# CONNECTOR.net
KiCad netlist of a schematic drawn in Altium Designer
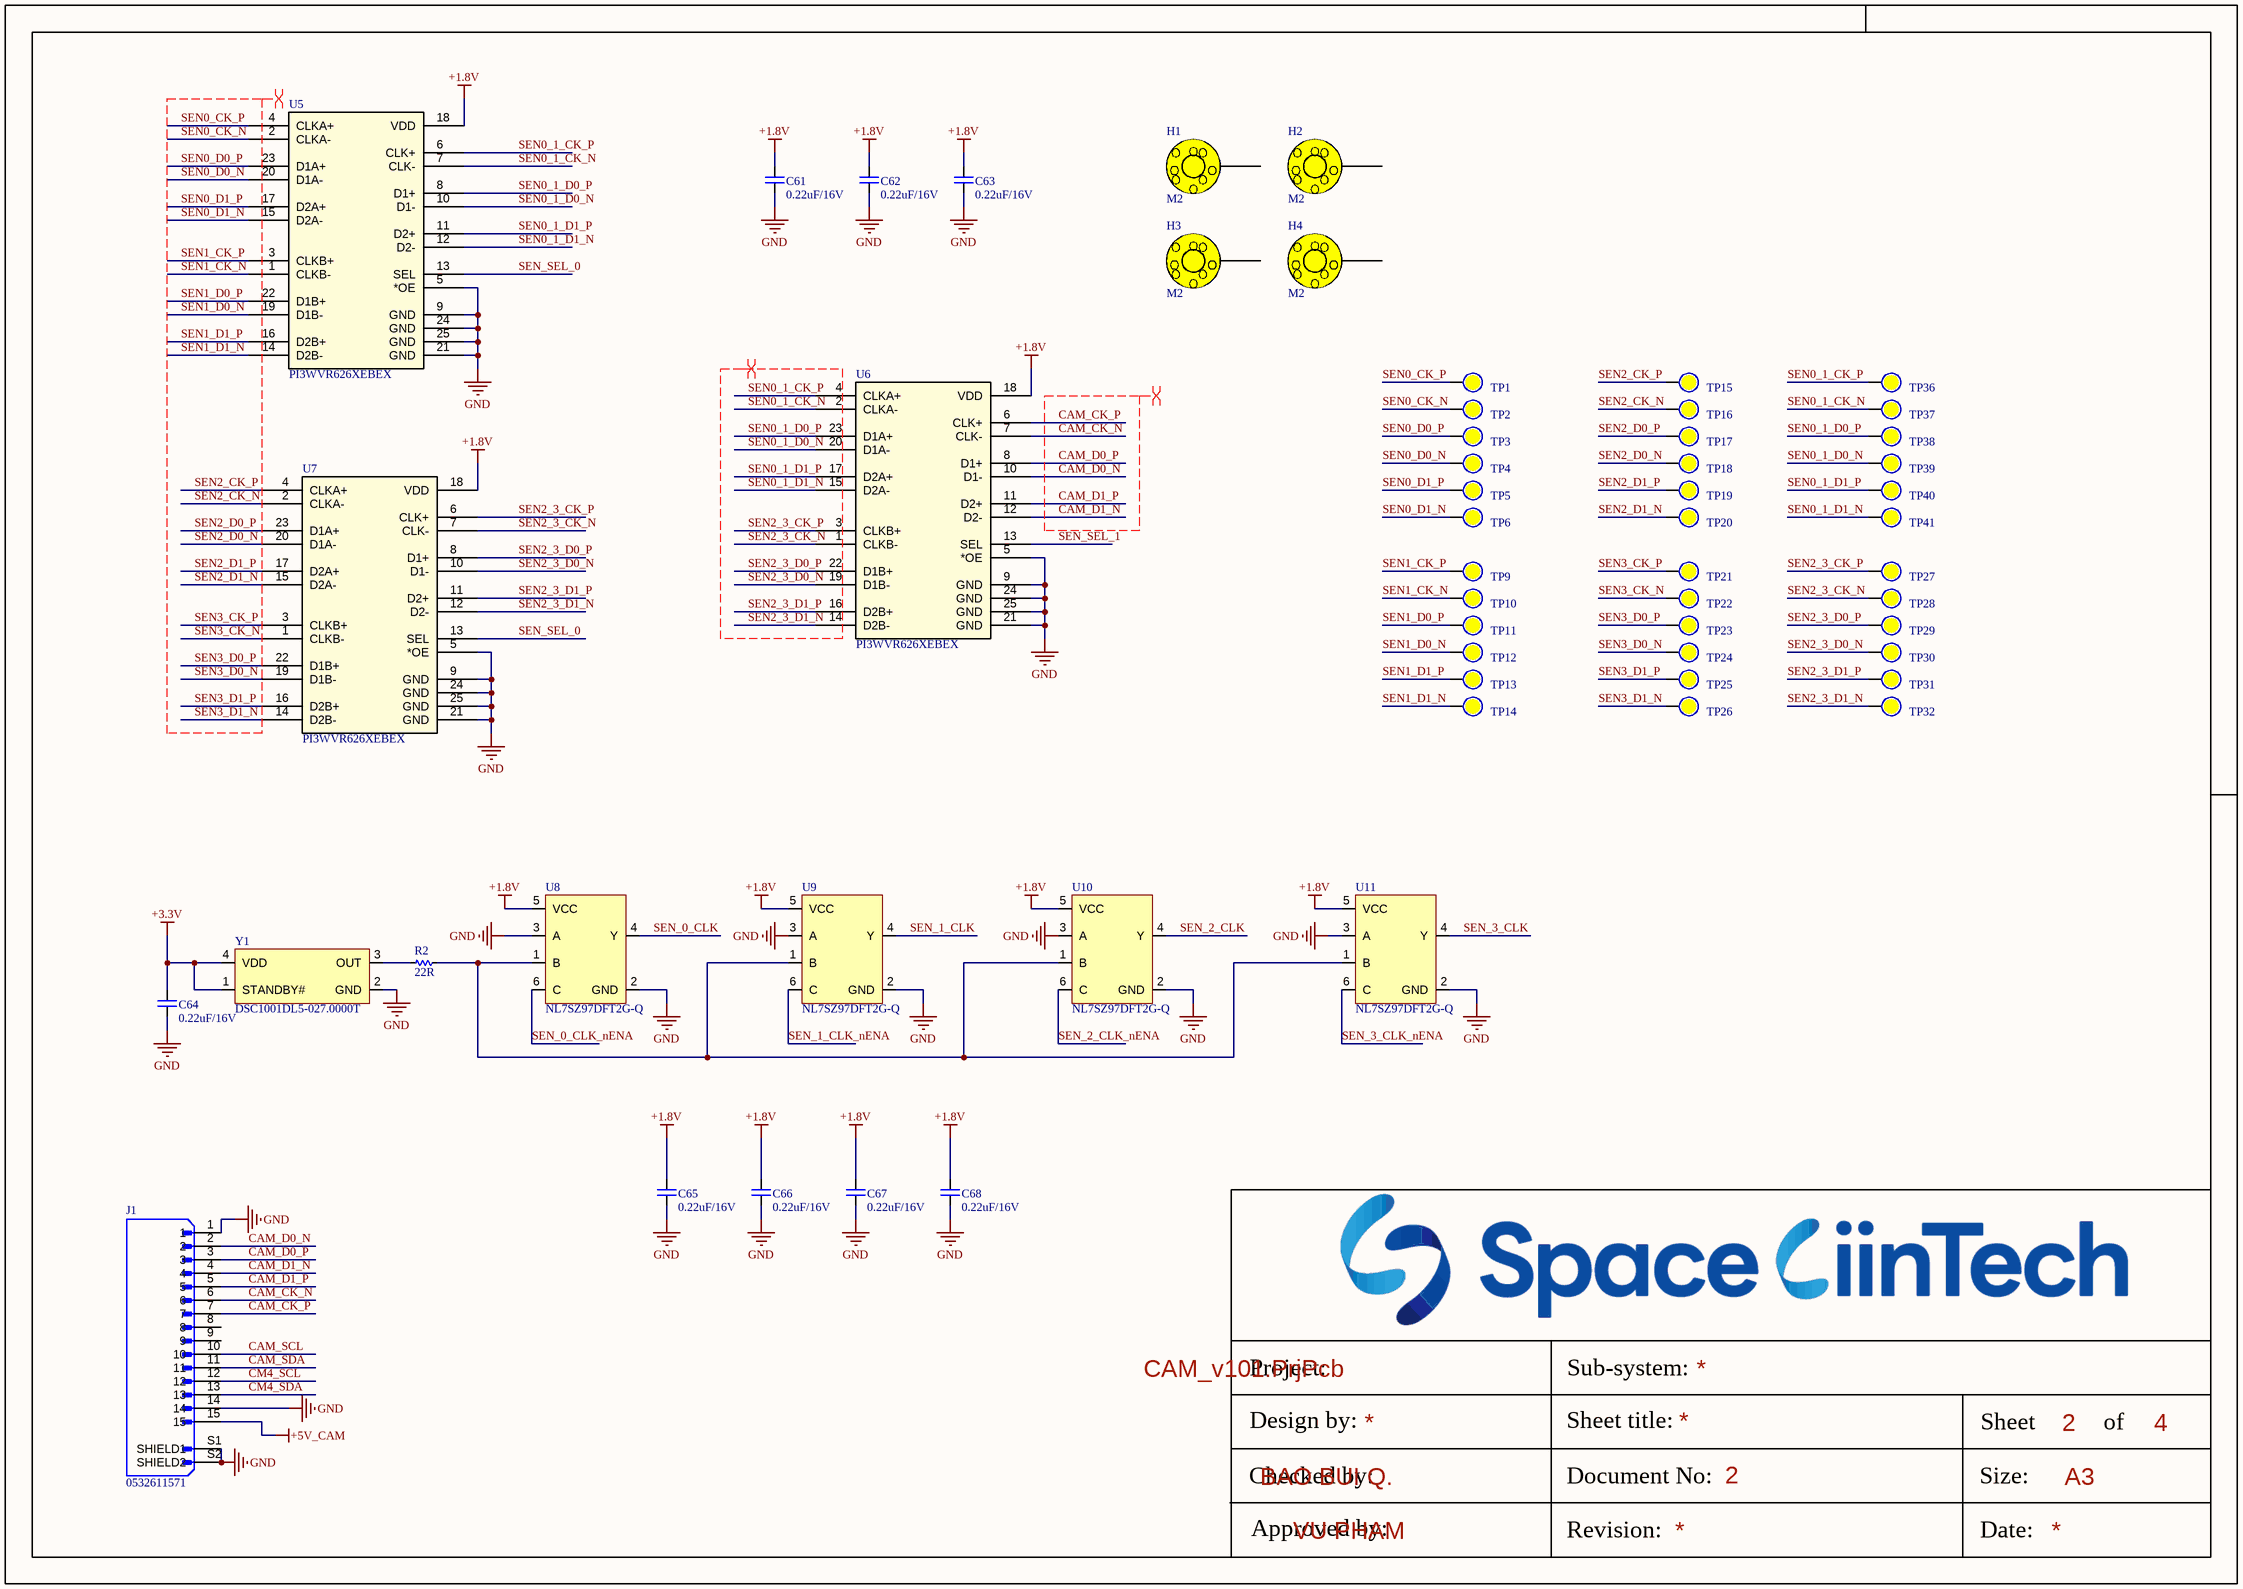
[diagram p0: CONNECTOR.SchDoc]

(export (version "E")
  (design (tool "Eeschema 10.0.6"))
  (components
    (comp (ref "C61")
      (value "0.22uF/16V")
      (footprint "CAP_C_1005X60")
      (description "CAP_Chip")
      (libsource (lib "LABLIB") (part "CAP_SMD"))
    )
    (comp (ref "C62")
      (value "0.22uF/16V")
      (footprint "CAP_C_1005X60")
      (description "CAP_Chip")
      (libsource (lib "LABLIB") (part "CAP_SMD"))
    )
    (comp (ref "C63")
      (value "0.22uF/16V")
      (footprint "CAP_C_1005X60")
      (description "CAP_Chip")
      (libsource (lib "LABLIB") (part "CAP_SMD"))
    )
    (comp (ref "C64")
      (value "0.22uF/16V")
      (footprint "CAP_C_1005X60")
      (description "CAP_Chip")
      (libsource (lib "LABLIB") (part "CAP_SMD"))
    )
    (comp (ref "C65")
      (value "0.22uF/16V")
      (footprint "CAP_C_1005X60")
      (description "CAP_Chip")
      (libsource (lib "LABLIB") (part "CAP_SMD"))
    )
    (comp (ref "C66")
      (value "0.22uF/16V")
      (footprint "CAP_C_1005X60")
      (description "CAP_Chip")
      (libsource (lib "LABLIB") (part "CAP_SMD"))
    )
    (comp (ref "C67")
      (value "0.22uF/16V")
      (footprint "CAP_C_1005X60")
      (description "CAP_Chip")
      (libsource (lib "LABLIB") (part "CAP_SMD"))
    )
    (comp (ref "C68")
      (value "0.22uF/16V")
      (footprint "CAP_C_1005X60")
      (description "CAP_Chip")
      (libsource (lib "LABLIB") (part "CAP_SMD"))
    )
    (comp (ref "H1") (value "M2") (footprint "HEX-2.2mm") (libsource (lib "hex_M3") (part "HEX-M3")))
    (comp (ref "H2") (value "M2") (footprint "HEX-2.2mm") (libsource (lib "hex_M3") (part "HEX-M3")))
    (comp (ref "H3") (value "M2") (footprint "HEX-2.2mm") (libsource (lib "hex_M3") (part "HEX-M3")))
    (comp (ref "H4") (value "M2") (footprint "HEX-2.2mm") (libsource (lib "hex_M3") (part "HEX-M3")))
    (comp (ref "J1")
      (value "0532611571")
      (footprint "0532611571")
      (description "Conn Shrouded Header (4 Sides) HDR 15 POS 1.25mm Solder RA Side Entry SMD PicoBladeâ„¢ T/R")
      (fields (field (name "MP") "532611571") (field (name "MF") "Molex"))
      (libsource (lib "EXP_HW_V2") (part "CONN_SMD_15"))
    )
    (comp (ref "R2")
      (value "22R")
      (footprint "RES_C_1005X40")
      (description "RES-Chip")
      (fields
        (field (name "MANUFACTURER") "Generic Components")
        (field (name "PUBLISHER") "Altium Hobart Technology Centre")
      )
      (libsource (lib "LABLIB") (part "RES-SMD"))
    )
    (comp (ref "TP1")
      (value "~")
      (footprint "Testpoint_60")
      (description "Test Point")
      (libsource (lib "LABLIB") (part "Test Point"))
    )
    (comp (ref "TP2")
      (value "~")
      (footprint "Testpoint_60")
      (description "Test Point")
      (libsource (lib "LABLIB") (part "Test Point"))
    )
    (comp (ref "TP3")
      (value "~")
      (footprint "Testpoint_60")
      (description "Test Point")
      (libsource (lib "LABLIB") (part "Test Point"))
    )
    (comp (ref "TP4")
      (value "~")
      (footprint "Testpoint_60")
      (description "Test Point")
      (libsource (lib "LABLIB") (part "Test Point"))
    )
    (comp (ref "TP5")
      (value "~")
      (footprint "Testpoint_60")
      (description "Test Point")
      (libsource (lib "LABLIB") (part "Test Point"))
    )
    (comp (ref "TP6")
      (value "~")
      (footprint "Testpoint_60")
      (description "Test Point")
      (libsource (lib "LABLIB") (part "Test Point"))
    )
    (comp (ref "TP9")
      (value "~")
      (footprint "Testpoint_60")
      (description "Test Point")
      (libsource (lib "LABLIB") (part "Test Point"))
    )
    (comp (ref "TP10")
      (value "~")
      (footprint "Testpoint_60")
      (description "Test Point")
      (libsource (lib "LABLIB") (part "Test Point"))
    )
    (comp (ref "TP11")
      (value "~")
      (footprint "Testpoint_60")
      (description "Test Point")
      (libsource (lib "LABLIB") (part "Test Point"))
    )
    (comp (ref "TP12")
      (value "~")
      (footprint "Testpoint_60")
      (description "Test Point")
      (libsource (lib "LABLIB") (part "Test Point"))
    )
    (comp (ref "TP13")
      (value "~")
      (footprint "Testpoint_60")
      (description "Test Point")
      (libsource (lib "LABLIB") (part "Test Point"))
    )
    (comp (ref "TP14")
      (value "~")
      (footprint "Testpoint_60")
      (description "Test Point")
      (libsource (lib "LABLIB") (part "Test Point"))
    )
    (comp (ref "TP15")
      (value "~")
      (footprint "Testpoint_60")
      (description "Test Point")
      (libsource (lib "LABLIB") (part "Test Point"))
    )
    (comp (ref "TP16")
      (value "~")
      (footprint "Testpoint_60")
      (description "Test Point")
      (libsource (lib "LABLIB") (part "Test Point"))
    )
    (comp (ref "TP17")
      (value "~")
      (footprint "Testpoint_60")
      (description "Test Point")
      (libsource (lib "LABLIB") (part "Test Point"))
    )
    (comp (ref "TP18")
      (value "~")
      (footprint "Testpoint_60")
      (description "Test Point")
      (libsource (lib "LABLIB") (part "Test Point"))
    )
    (comp (ref "TP19")
      (value "~")
      (footprint "Testpoint_60")
      (description "Test Point")
      (libsource (lib "LABLIB") (part "Test Point"))
    )
    (comp (ref "TP20")
      (value "~")
      (footprint "Testpoint_60")
      (description "Test Point")
      (libsource (lib "LABLIB") (part "Test Point"))
    )
    (comp (ref "TP21")
      (value "~")
      (footprint "Testpoint_60")
      (description "Test Point")
      (libsource (lib "LABLIB") (part "Test Point"))
    )
    (comp (ref "TP22")
      (value "~")
      (footprint "Testpoint_60")
      (description "Test Point")
      (libsource (lib "LABLIB") (part "Test Point"))
    )
    (comp (ref "TP23")
      (value "~")
      (footprint "Testpoint_60")
      (description "Test Point")
      (libsource (lib "LABLIB") (part "Test Point"))
    )
    (comp (ref "TP24")
      (value "~")
      (footprint "Testpoint_60")
      (description "Test Point")
      (libsource (lib "LABLIB") (part "Test Point"))
    )
    (comp (ref "TP25")
      (value "~")
      (footprint "Testpoint_60")
      (description "Test Point")
      (libsource (lib "LABLIB") (part "Test Point"))
    )
    (comp (ref "TP26")
      (value "~")
      (footprint "Testpoint_60")
      (description "Test Point")
      (libsource (lib "LABLIB") (part "Test Point"))
    )
    (comp (ref "TP27")
      (value "~")
      (footprint "Testpoint_50")
      (description "Test Point")
      (libsource (lib "LABLIB") (part "Test Point"))
    )
    (comp (ref "TP28")
      (value "~")
      (footprint "Testpoint_50")
      (description "Test Point")
      (libsource (lib "LABLIB") (part "Test Point"))
    )
    (comp (ref "TP29")
      (value "~")
      (footprint "Testpoint_50")
      (description "Test Point")
      (libsource (lib "LABLIB") (part "Test Point"))
    )
    (comp (ref "TP30")
      (value "~")
      (footprint "Testpoint_50")
      (description "Test Point")
      (libsource (lib "LABLIB") (part "Test Point"))
    )
    (comp (ref "TP31")
      (value "~")
      (footprint "Testpoint_50")
      (description "Test Point")
      (libsource (lib "LABLIB") (part "Test Point"))
    )
    (comp (ref "TP32")
      (value "~")
      (footprint "Testpoint_50")
      (description "Test Point")
      (libsource (lib "LABLIB") (part "Test Point"))
    )
    (comp (ref "TP36")
      (value "~")
      (footprint "Testpoint_50")
      (description "Test Point")
      (libsource (lib "LABLIB") (part "Test Point"))
    )
    (comp (ref "TP37")
      (value "~")
      (footprint "Testpoint_50")
      (description "Test Point")
      (libsource (lib "LABLIB") (part "Test Point"))
    )
    (comp (ref "TP38")
      (value "~")
      (footprint "Testpoint_50")
      (description "Test Point")
      (libsource (lib "LABLIB") (part "Test Point"))
    )
    (comp (ref "TP39")
      (value "~")
      (footprint "Testpoint_50")
      (description "Test Point")
      (libsource (lib "LABLIB") (part "Test Point"))
    )
    (comp (ref "TP40")
      (value "~")
      (footprint "Testpoint_50")
      (description "Test Point")
      (libsource (lib "LABLIB") (part "Test Point"))
    )
    (comp (ref "TP41")
      (value "~")
      (footprint "Testpoint_50")
      (description "Test Point")
      (libsource (lib "LABLIB") (part "Test Point"))
    )
    (comp (ref "U5")
      (value "PI3WVR626XEBEX")
      (footprint "PI3WVR626XEBEX_DIO_2")
      (libsource (lib "CAMERA_SchLib") (part "PI3WVR626XEBEX"))
    )
    (comp (ref "U6")
      (value "PI3WVR626XEBEX")
      (footprint "PI3WVR626XEBEX_DIO_2")
      (libsource (lib "CAMERA_SchLib") (part "PI3WVR626XEBEX"))
    )
    (comp (ref "U7")
      (value "PI3WVR626XEBEX")
      (footprint "PI3WVR626XEBEX_DIO_2")
      (libsource (lib "CAMERA_SchLib") (part "PI3WVR626XEBEX"))
    )
    (comp (ref "U8")
      (value "NL7SZ97DFT2G-Q")
      (footprint "SC-88")
      (libsource (lib "CAMERA_SchLib") (part "IC_FLEXLOGIC_NL7SZ97DFT2G-Q"))
    )
    (comp (ref "U9")
      (value "NL7SZ97DFT2G-Q")
      (footprint "SC-88")
      (libsource (lib "CAMERA_SchLib") (part "IC_FLEXLOGIC_NL7SZ97DFT2G-Q"))
    )
    (comp (ref "U10")
      (value "NL7SZ97DFT2G-Q")
      (footprint "SC-88")
      (libsource (lib "CAMERA_SchLib") (part "IC_FLEXLOGIC_NL7SZ97DFT2G-Q"))
    )
    (comp (ref "U11")
      (value "NL7SZ97DFT2G-Q")
      (footprint "SC-88")
      (libsource (lib "CAMERA_SchLib") (part "IC_FLEXLOGIC_NL7SZ97DFT2G-Q"))
    )
    (comp (ref "Y1")
      (value "DSC1001DL5-027.0000T")
      (footprint "OSCDFN250X200X89-4N")
      (libsource (lib "CAMERA_SchLib") (part "Y_OSC27MHz_DSC1001DL5-027.0000T"))
    )
  )
  (nets
    (net (code "1") (name "+1.8V") (class "Default")
      (node (ref "C61") (pin "2") (pinfunction "2_2") (pintype "passive"))
      (node (ref "C62") (pin "2") (pinfunction "2_2") (pintype "passive"))
      (node (ref "C63") (pin "2") (pinfunction "2_2") (pintype "passive"))
      (node (ref "C65") (pin "2") (pinfunction "2_2") (pintype "passive"))
      (node (ref "C66") (pin "2") (pinfunction "2_2") (pintype "passive"))
      (node (ref "C67") (pin "2") (pinfunction "2_2") (pintype "passive"))
      (node (ref "C68") (pin "2") (pinfunction "2_2") (pintype "passive"))
      (node (ref "U10") (pin "5") (pinfunction "VCC_5") (pintype "passive"))
      (node (ref "U11") (pin "5") (pinfunction "VCC_5") (pintype "passive"))
      (node (ref "U5") (pin "18") (pinfunction "VDD_18") (pintype "passive"))
      (node (ref "U6") (pin "18") (pinfunction "VDD_18") (pintype "passive"))
      (node (ref "U7") (pin "18") (pinfunction "VDD_18") (pintype "passive"))
      (node (ref "U8") (pin "5") (pinfunction "VCC_5") (pintype "passive"))
      (node (ref "U9") (pin "5") (pinfunction "VCC_5") (pintype "passive"))
    )
    (net (code "2") (name "+3.3V") (class "Default")
      (node (ref "C64") (pin "2") (pinfunction "2_2") (pintype "passive"))
      (node (ref "Y1") (pin "1") (pinfunction "STANDBY#_1") (pintype "passive"))
      (node (ref "Y1") (pin "4") (pinfunction "VDD_4") (pintype "passive"))
    )
    (net (code "3") (name "+5V_CAM") (class "Default")
      (node (ref "J1") (pin "15") (pinfunction "15_15") (pintype "passive"))
    )
    (net (code "4") (name "/CAM_CK_N") (class "Default")
      (node (ref "J1") (pin "6") (pinfunction "6_6") (pintype "passive"))
      (node (ref "U6") (pin "7") (pinfunction "CLK-_7") (pintype "passive"))
    )
    (net (code "5") (name "/CAM_CK_P") (class "Default")
      (node (ref "J1") (pin "7") (pinfunction "7_7") (pintype "passive"))
      (node (ref "U6") (pin "6") (pinfunction "CLK+_6") (pintype "passive"))
    )
    (net (code "6") (name "/CAM_D0_N") (class "Default")
      (node (ref "J1") (pin "2") (pinfunction "2_2") (pintype "passive"))
      (node (ref "U6") (pin "10") (pinfunction "D1-_10") (pintype "passive"))
    )
    (net (code "7") (name "/CAM_D0_P") (class "Default")
      (node (ref "J1") (pin "3") (pinfunction "3_3") (pintype "passive"))
      (node (ref "U6") (pin "8") (pinfunction "D1+_8") (pintype "passive"))
    )
    (net (code "8") (name "/CAM_D1_N") (class "Default")
      (node (ref "J1") (pin "4") (pinfunction "4_4") (pintype "passive"))
      (node (ref "U6") (pin "12") (pinfunction "D2-_12") (pintype "passive"))
    )
    (net (code "9") (name "/CAM_D1_P") (class "Default")
      (node (ref "J1") (pin "5") (pinfunction "5_5") (pintype "passive"))
      (node (ref "U6") (pin "11") (pinfunction "D2+_11") (pintype "passive"))
    )
    (net (code "10") (name "/CAM_SCL") (class "Default")
      (node (ref "J1") (pin "10") (pinfunction "10_10") (pintype "passive"))
    )
    (net (code "11") (name "/CAM_SDA") (class "Default")
      (node (ref "J1") (pin "11") (pinfunction "11_11") (pintype "passive"))
    )
    (net (code "12") (name "/CM4_SCL") (class "Default")
      (node (ref "J1") (pin "12") (pinfunction "12_12") (pintype "passive"))
    )
    (net (code "13") (name "/CM4_SDA") (class "Default")
      (node (ref "J1") (pin "13") (pinfunction "13_13") (pintype "passive"))
    )
    (net (code "14") (name "/SEN0_1_CK_N") (class "Default")
      (node (ref "TP37") (pin "0") (pinfunction "0_0") (pintype "passive"))
      (node (ref "U5") (pin "7") (pinfunction "CLK-_7") (pintype "passive"))
      (node (ref "U6") (pin "2") (pinfunction "CLKA-_2") (pintype "passive"))
    )
    (net (code "15") (name "/SEN0_1_CK_P") (class "Default")
      (node (ref "TP36") (pin "0") (pinfunction "0_0") (pintype "passive"))
      (node (ref "U5") (pin "6") (pinfunction "CLK+_6") (pintype "passive"))
      (node (ref "U6") (pin "4") (pinfunction "CLKA+_4") (pintype "passive"))
    )
    (net (code "16") (name "/SEN0_1_D0_N") (class "Default")
      (node (ref "TP39") (pin "0") (pinfunction "0_0") (pintype "passive"))
      (node (ref "U5") (pin "10") (pinfunction "D1-_10") (pintype "passive"))
      (node (ref "U6") (pin "20") (pinfunction "D1A-_20") (pintype "passive"))
    )
    (net (code "17") (name "/SEN0_1_D0_P") (class "Default")
      (node (ref "TP38") (pin "0") (pinfunction "0_0") (pintype "passive"))
      (node (ref "U5") (pin "8") (pinfunction "D1+_8") (pintype "passive"))
      (node (ref "U6") (pin "23") (pinfunction "D1A+_23") (pintype "passive"))
    )
    (net (code "18") (name "/SEN0_1_D1_N") (class "Default")
      (node (ref "TP41") (pin "0") (pinfunction "0_0") (pintype "passive"))
      (node (ref "U5") (pin "12") (pinfunction "D2-_12") (pintype "passive"))
      (node (ref "U6") (pin "15") (pinfunction "D2A-_15") (pintype "passive"))
    )
    (net (code "19") (name "/SEN0_1_D1_P") (class "Default")
      (node (ref "TP40") (pin "0") (pinfunction "0_0") (pintype "passive"))
      (node (ref "U5") (pin "11") (pinfunction "D2+_11") (pintype "passive"))
      (node (ref "U6") (pin "17") (pinfunction "D2A+_17") (pintype "passive"))
    )
    (net (code "20") (name "/SEN0_CK_N") (class "Default")
      (node (ref "TP2") (pin "0") (pinfunction "0_0") (pintype "passive"))
      (node (ref "U5") (pin "2") (pinfunction "CLKA-_2") (pintype "passive"))
    )
    (net (code "21") (name "/SEN0_CK_P") (class "Default")
      (node (ref "TP1") (pin "0") (pinfunction "0_0") (pintype "passive"))
      (node (ref "U5") (pin "4") (pinfunction "CLKA+_4") (pintype "passive"))
    )
    (net (code "22") (name "/SEN0_D0_N") (class "Default")
      (node (ref "TP4") (pin "0") (pinfunction "0_0") (pintype "passive"))
      (node (ref "U5") (pin "20") (pinfunction "D1A-_20") (pintype "passive"))
    )
    (net (code "23") (name "/SEN0_D0_P") (class "Default")
      (node (ref "TP3") (pin "0") (pinfunction "0_0") (pintype "passive"))
      (node (ref "U5") (pin "23") (pinfunction "D1A+_23") (pintype "passive"))
    )
    (net (code "24") (name "/SEN0_D1_N") (class "Default")
      (node (ref "TP6") (pin "0") (pinfunction "0_0") (pintype "passive"))
      (node (ref "U5") (pin "15") (pinfunction "D2A-_15") (pintype "passive"))
    )
    (net (code "25") (name "/SEN0_D1_P") (class "Default")
      (node (ref "TP5") (pin "0") (pinfunction "0_0") (pintype "passive"))
      (node (ref "U5") (pin "17") (pinfunction "D2A+_17") (pintype "passive"))
    )
    (net (code "26") (name "/SEN1_CK_N") (class "Default")
      (node (ref "TP10") (pin "0") (pinfunction "0_0") (pintype "passive"))
      (node (ref "U5") (pin "1") (pinfunction "CLKB-_1") (pintype "passive"))
    )
    (net (code "27") (name "/SEN1_CK_P") (class "Default")
      (node (ref "TP9") (pin "0") (pinfunction "0_0") (pintype "passive"))
      (node (ref "U5") (pin "3") (pinfunction "CLKB+_3") (pintype "passive"))
    )
    (net (code "28") (name "/SEN1_D0_N") (class "Default")
      (node (ref "TP12") (pin "0") (pinfunction "0_0") (pintype "passive"))
      (node (ref "U5") (pin "19") (pinfunction "D1B-_19") (pintype "passive"))
    )
    (net (code "29") (name "/SEN1_D0_P") (class "Default")
      (node (ref "TP11") (pin "0") (pinfunction "0_0") (pintype "passive"))
      (node (ref "U5") (pin "22") (pinfunction "D1B+_22") (pintype "passive"))
    )
    (net (code "30") (name "/SEN1_D1_N") (class "Default")
      (node (ref "TP14") (pin "0") (pinfunction "0_0") (pintype "passive"))
      (node (ref "U5") (pin "14") (pinfunction "D2B-_14") (pintype "passive"))
    )
    (net (code "31") (name "/SEN1_D1_P") (class "Default")
      (node (ref "TP13") (pin "0") (pinfunction "0_0") (pintype "passive"))
      (node (ref "U5") (pin "16") (pinfunction "D2B+_16") (pintype "passive"))
    )
    (net (code "32") (name "/SEN2_3_CK_N") (class "Default")
      (node (ref "TP28") (pin "0") (pinfunction "0_0") (pintype "passive"))
      (node (ref "U6") (pin "1") (pinfunction "CLKB-_1") (pintype "passive"))
      (node (ref "U7") (pin "7") (pinfunction "CLK-_7") (pintype "passive"))
    )
    (net (code "33") (name "/SEN2_3_CK_P") (class "Default")
      (node (ref "TP27") (pin "0") (pinfunction "0_0") (pintype "passive"))
      (node (ref "U6") (pin "3") (pinfunction "CLKB+_3") (pintype "passive"))
      (node (ref "U7") (pin "6") (pinfunction "CLK+_6") (pintype "passive"))
    )
    (net (code "34") (name "/SEN2_3_D0_N") (class "Default")
      (node (ref "TP30") (pin "0") (pinfunction "0_0") (pintype "passive"))
      (node (ref "U6") (pin "19") (pinfunction "D1B-_19") (pintype "passive"))
      (node (ref "U7") (pin "10") (pinfunction "D1-_10") (pintype "passive"))
    )
    (net (code "35") (name "/SEN2_3_D0_P") (class "Default")
      (node (ref "TP29") (pin "0") (pinfunction "0_0") (pintype "passive"))
      (node (ref "U6") (pin "22") (pinfunction "D1B+_22") (pintype "passive"))
      (node (ref "U7") (pin "8") (pinfunction "D1+_8") (pintype "passive"))
    )
    (net (code "36") (name "/SEN2_3_D1_N") (class "Default")
      (node (ref "TP32") (pin "0") (pinfunction "0_0") (pintype "passive"))
      (node (ref "U6") (pin "14") (pinfunction "D2B-_14") (pintype "passive"))
      (node (ref "U7") (pin "12") (pinfunction "D2-_12") (pintype "passive"))
    )
    (net (code "37") (name "/SEN2_3_D1_P") (class "Default")
      (node (ref "TP31") (pin "0") (pinfunction "0_0") (pintype "passive"))
      (node (ref "U6") (pin "16") (pinfunction "D2B+_16") (pintype "passive"))
      (node (ref "U7") (pin "11") (pinfunction "D2+_11") (pintype "passive"))
    )
    (net (code "38") (name "/SEN2_CK_N") (class "Default")
      (node (ref "TP16") (pin "0") (pinfunction "0_0") (pintype "passive"))
      (node (ref "U7") (pin "2") (pinfunction "CLKA-_2") (pintype "passive"))
    )
    (net (code "39") (name "/SEN2_CK_P") (class "Default")
      (node (ref "TP15") (pin "0") (pinfunction "0_0") (pintype "passive"))
      (node (ref "U7") (pin "4") (pinfunction "CLKA+_4") (pintype "passive"))
    )
    (net (code "40") (name "/SEN2_D0_N") (class "Default")
      (node (ref "TP18") (pin "0") (pinfunction "0_0") (pintype "passive"))
      (node (ref "U7") (pin "20") (pinfunction "D1A-_20") (pintype "passive"))
    )
    (net (code "41") (name "/SEN2_D0_P") (class "Default")
      (node (ref "TP17") (pin "0") (pinfunction "0_0") (pintype "passive"))
      (node (ref "U7") (pin "23") (pinfunction "D1A+_23") (pintype "passive"))
    )
    (net (code "42") (name "/SEN2_D1_N") (class "Default")
      (node (ref "TP20") (pin "0") (pinfunction "0_0") (pintype "passive"))
      (node (ref "U7") (pin "15") (pinfunction "D2A-_15") (pintype "passive"))
    )
    (net (code "43") (name "/SEN2_D1_P") (class "Default")
      (node (ref "TP19") (pin "0") (pinfunction "0_0") (pintype "passive"))
      (node (ref "U7") (pin "17") (pinfunction "D2A+_17") (pintype "passive"))
    )
    (net (code "44") (name "/SEN3_CK_N") (class "Default")
      (node (ref "TP22") (pin "0") (pinfunction "0_0") (pintype "passive"))
      (node (ref "U7") (pin "1") (pinfunction "CLKB-_1") (pintype "passive"))
    )
    (net (code "45") (name "/SEN3_CK_P") (class "Default")
      (node (ref "TP21") (pin "0") (pinfunction "0_0") (pintype "passive"))
      (node (ref "U7") (pin "3") (pinfunction "CLKB+_3") (pintype "passive"))
    )
    (net (code "46") (name "/SEN3_D0_N") (class "Default")
      (node (ref "TP24") (pin "0") (pinfunction "0_0") (pintype "passive"))
      (node (ref "U7") (pin "19") (pinfunction "D1B-_19") (pintype "passive"))
    )
    (net (code "47") (name "/SEN3_D0_P") (class "Default")
      (node (ref "TP23") (pin "0") (pinfunction "0_0") (pintype "passive"))
      (node (ref "U7") (pin "22") (pinfunction "D1B+_22") (pintype "passive"))
    )
    (net (code "48") (name "/SEN3_D1_N") (class "Default")
      (node (ref "TP26") (pin "0") (pinfunction "0_0") (pintype "passive"))
      (node (ref "U7") (pin "14") (pinfunction "D2B-_14") (pintype "passive"))
    )
    (net (code "49") (name "/SEN3_D1_P") (class "Default")
      (node (ref "TP25") (pin "0") (pinfunction "0_0") (pintype "passive"))
      (node (ref "U7") (pin "16") (pinfunction "D2B+_16") (pintype "passive"))
    )
    (net (code "50") (name "/SEN_0_CLK") (class "Default")
      (node (ref "U8") (pin "4") (pinfunction "Y_4") (pintype "passive"))
    )
    (net (code "51") (name "/SEN_0_CLK_nENA") (class "Default")
      (node (ref "U8") (pin "6") (pinfunction "C_6") (pintype "passive"))
    )
    (net (code "52") (name "/SEN_1_CLK") (class "Default")
      (node (ref "U9") (pin "4") (pinfunction "Y_4") (pintype "passive"))
    )
    (net (code "53") (name "/SEN_1_CLK_nENA") (class "Default")
      (node (ref "U9") (pin "6") (pinfunction "C_6") (pintype "passive"))
    )
    (net (code "54") (name "/SEN_2_CLK") (class "Default")
      (node (ref "U10") (pin "4") (pinfunction "Y_4") (pintype "passive"))
    )
    (net (code "55") (name "/SEN_2_CLK_nENA") (class "Default")
      (node (ref "U10") (pin "6") (pinfunction "C_6") (pintype "passive"))
    )
    (net (code "56") (name "/SEN_3_CLK") (class "Default")
      (node (ref "U11") (pin "4") (pinfunction "Y_4") (pintype "passive"))
    )
    (net (code "57") (name "/SEN_3_CLK_nENA") (class "Default")
      (node (ref "U11") (pin "6") (pinfunction "C_6") (pintype "passive"))
    )
    (net (code "58") (name "/SEN_SEL_0") (class "Default")
      (node (ref "U5") (pin "13") (pinfunction "SEL_13") (pintype "passive"))
      (node (ref "U7") (pin "13") (pinfunction "SEL_13") (pintype "passive"))
    )
    (net (code "59") (name "/SEN_SEL_1") (class "Default")
      (node (ref "U6") (pin "13") (pinfunction "SEL_13") (pintype "passive"))
    )
    (net (code "60") (name "GND") (class "Default")
      (node (ref "C61") (pin "1") (pinfunction "1_1") (pintype "passive"))
      (node (ref "C62") (pin "1") (pinfunction "1_1") (pintype "passive"))
      (node (ref "C63") (pin "1") (pinfunction "1_1") (pintype "passive"))
      (node (ref "C64") (pin "1") (pinfunction "1_1") (pintype "passive"))
      (node (ref "C65") (pin "1") (pinfunction "1_1") (pintype "passive"))
      (node (ref "C66") (pin "1") (pinfunction "1_1") (pintype "passive"))
      (node (ref "C67") (pin "1") (pinfunction "1_1") (pintype "passive"))
      (node (ref "C68") (pin "1") (pinfunction "1_1") (pintype "passive"))
      (node (ref "J1") (pin "1") (pinfunction "1_1") (pintype "passive"))
      (node (ref "J1") (pin "14") (pinfunction "14_14") (pintype "passive"))
      (node (ref "J1") (pin "S1") (pinfunction "SHIELD1_S1") (pintype "passive"))
      (node (ref "J1") (pin "S2") (pinfunction "SHIELD2_S2") (pintype "passive"))
      (node (ref "U10") (pin "2") (pinfunction "GND_2") (pintype "passive"))
      (node (ref "U10") (pin "3") (pinfunction "A_3") (pintype "passive"))
      (node (ref "U11") (pin "2") (pinfunction "GND_2") (pintype "passive"))
      (node (ref "U11") (pin "3") (pinfunction "A_3") (pintype "passive"))
      (node (ref "U5") (pin "21") (pinfunction "GND_21") (pintype "passive"))
      (node (ref "U5") (pin "24") (pinfunction "GND_24") (pintype "passive"))
      (node (ref "U5") (pin "25") (pinfunction "GND_25") (pintype "passive"))
      (node (ref "U5") (pin "5") (pinfunction "*OE_5") (pintype "passive"))
      (node (ref "U5") (pin "9") (pinfunction "GND_9") (pintype "passive"))
      (node (ref "U6") (pin "21") (pinfunction "GND_21") (pintype "passive"))
      (node (ref "U6") (pin "24") (pinfunction "GND_24") (pintype "passive"))
      (node (ref "U6") (pin "25") (pinfunction "GND_25") (pintype "passive"))
      (node (ref "U6") (pin "5") (pinfunction "*OE_5") (pintype "passive"))
      (node (ref "U6") (pin "9") (pinfunction "GND_9") (pintype "passive"))
      (node (ref "U7") (pin "21") (pinfunction "GND_21") (pintype "passive"))
      (node (ref "U7") (pin "24") (pinfunction "GND_24") (pintype "passive"))
      (node (ref "U7") (pin "25") (pinfunction "GND_25") (pintype "passive"))
      (node (ref "U7") (pin "5") (pinfunction "*OE_5") (pintype "passive"))
      (node (ref "U7") (pin "9") (pinfunction "GND_9") (pintype "passive"))
      (node (ref "U8") (pin "2") (pinfunction "GND_2") (pintype "passive"))
      (node (ref "U8") (pin "3") (pinfunction "A_3") (pintype "passive"))
      (node (ref "U9") (pin "2") (pinfunction "GND_2") (pintype "passive"))
      (node (ref "U9") (pin "3") (pinfunction "A_3") (pintype "passive"))
      (node (ref "Y1") (pin "2") (pinfunction "GND_2") (pintype "passive"))
    )
    (net (code "61") (name "Net-(U10-B)") (class "Default")
      (node (ref "R2") (pin "1") (pinfunction "1_1") (pintype "passive"))
      (node (ref "U10") (pin "1") (pinfunction "B_1") (pintype "passive"))
      (node (ref "U11") (pin "1") (pinfunction "B_1") (pintype "passive"))
      (node (ref "U8") (pin "1") (pinfunction "B_1") (pintype "passive"))
      (node (ref "U9") (pin "1") (pinfunction "B_1") (pintype "passive"))
    )
    (net (code "62") (name "Net-(Y1-OUT)") (class "Default")
      (node (ref "R2") (pin "2") (pinfunction "2_2") (pintype "passive"))
      (node (ref "Y1") (pin "3") (pinfunction "OUT_3") (pintype "passive"))
    )
    (net (code "63") (name "unconnected-(H1-Pad1)") (class "Default")
      (node (ref "H1") (pin "1") (pinfunction "1_1") (pintype "power_in"))
    )
    (net (code "64") (name "unconnected-(H2-Pad1)") (class "Default")
      (node (ref "H2") (pin "1") (pinfunction "1_1") (pintype "power_in"))
    )
    (net (code "65") (name "unconnected-(H3-Pad1)") (class "Default")
      (node (ref "H3") (pin "1") (pinfunction "1_1") (pintype "power_in"))
    )
    (net (code "66") (name "unconnected-(H4-Pad1)") (class "Default")
      (node (ref "H4") (pin "1") (pinfunction "1_1") (pintype "power_in"))
    )
    (net (code "67") (name "unconnected-(J1-Pad8)") (class "Default")
      (node (ref "J1") (pin "8") (pinfunction "8_8") (pintype "passive"))
    )
    (net (code "68") (name "unconnected-(J1-Pad9)") (class "Default")
      (node (ref "J1") (pin "9") (pinfunction "9_9") (pintype "passive"))
    )
  )
)
